# lab6_2020-12-28_18-12-07.net
KiCad netlist of a schematic drawn in EasyEDA
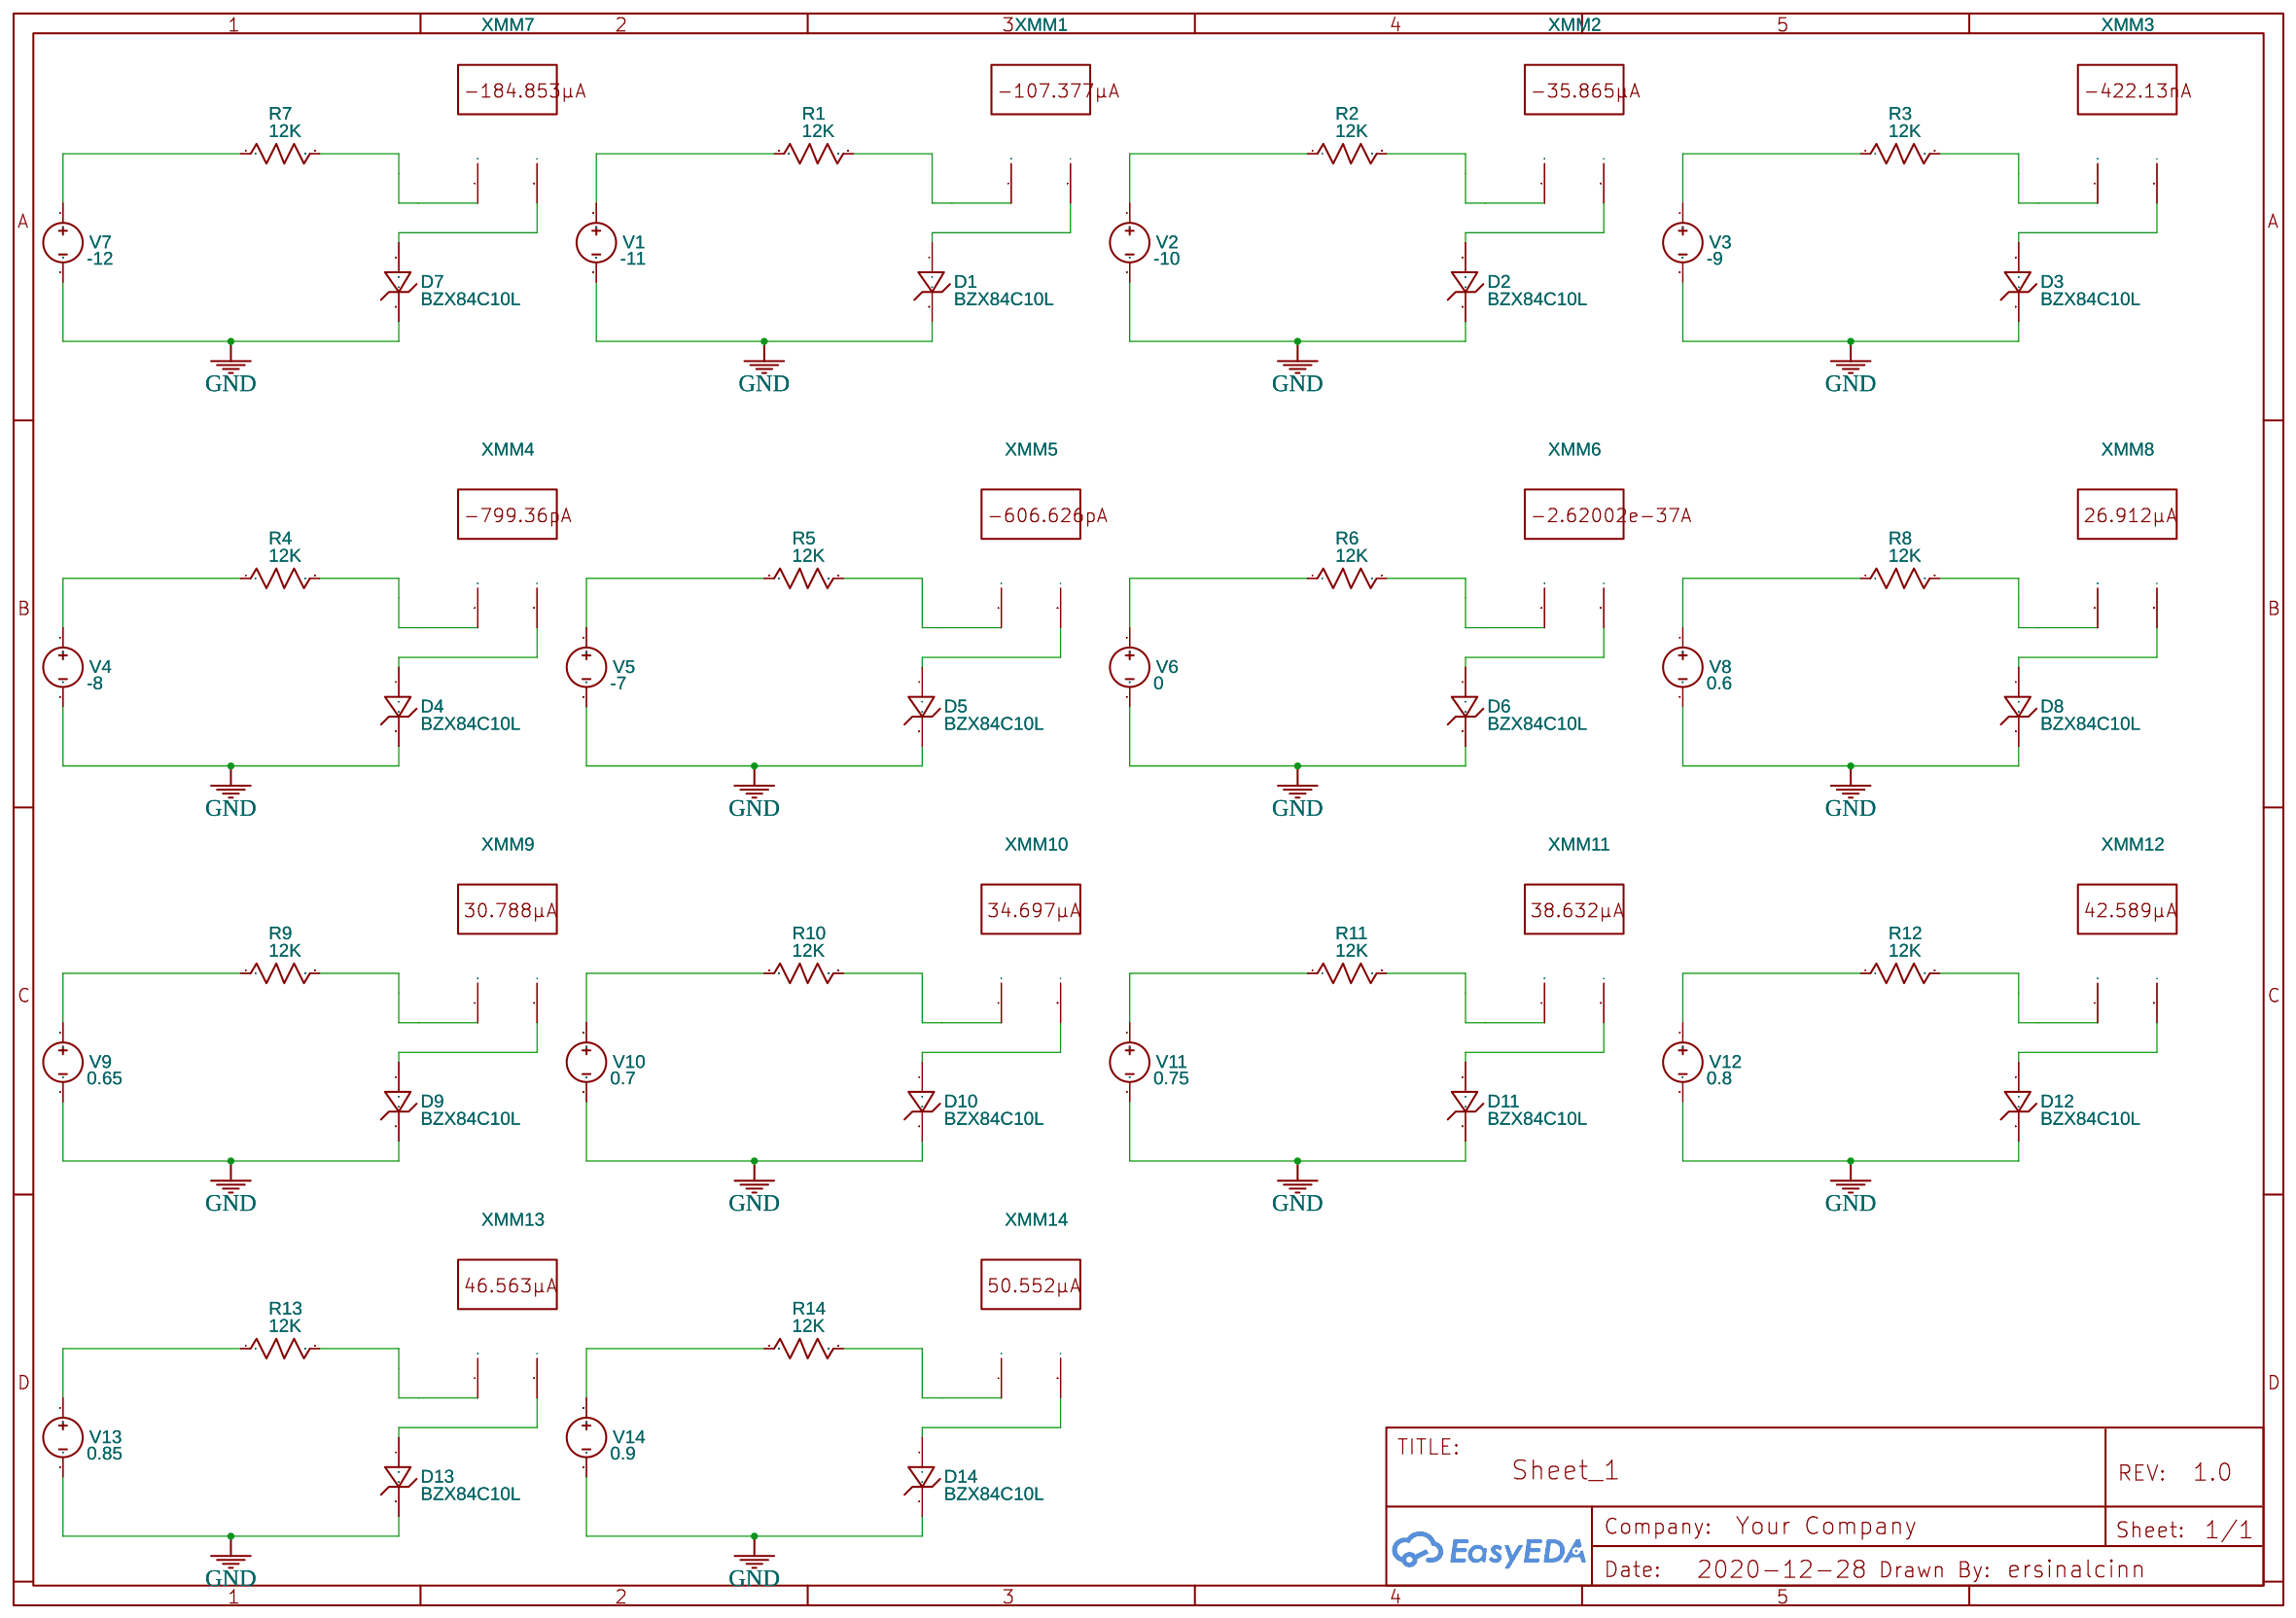
[diagram p0: schematic sheet]

(export (version "E")
  (design (tool "Eeschema 10.0.6"))
  (components
    (comp (ref "D1") (value "BZX84C10L") (libsource (lib "") (part "BZX84C10L")))
    (comp (ref "D2") (value "BZX84C10L") (libsource (lib "") (part "BZX84C10L")))
    (comp (ref "D3") (value "BZX84C10L") (libsource (lib "") (part "BZX84C10L")))
    (comp (ref "D4") (value "BZX84C10L") (libsource (lib "") (part "BZX84C10L")))
    (comp (ref "D5") (value "BZX84C10L") (libsource (lib "") (part "BZX84C10L")))
    (comp (ref "D6") (value "BZX84C10L") (libsource (lib "") (part "BZX84C10L")))
    (comp (ref "D7") (value "BZX84C10L") (libsource (lib "") (part "BZX84C10L")))
    (comp (ref "D8") (value "BZX84C10L") (libsource (lib "") (part "BZX84C10L")))
    (comp (ref "D9") (value "BZX84C10L") (libsource (lib "") (part "BZX84C10L")))
    (comp (ref "D10") (value "BZX84C10L") (libsource (lib "") (part "BZX84C10L")))
    (comp (ref "D11") (value "BZX84C10L") (libsource (lib "") (part "BZX84C10L")))
    (comp (ref "D12") (value "BZX84C10L") (libsource (lib "") (part "BZX84C10L")))
    (comp (ref "D13") (value "BZX84C10L") (libsource (lib "") (part "BZX84C10L")))
    (comp (ref "D14") (value "BZX84C10L") (libsource (lib "") (part "BZX84C10L")))
    (comp (ref "R1") (value "12K") (libsource (lib "") (part "Resistor_US")))
    (comp (ref "R2") (value "12K") (libsource (lib "") (part "Resistor_US")))
    (comp (ref "R3") (value "12K") (libsource (lib "") (part "Resistor_US")))
    (comp (ref "R4") (value "12K") (libsource (lib "") (part "Resistor_US")))
    (comp (ref "R5") (value "12K") (libsource (lib "") (part "Resistor_US")))
    (comp (ref "R6") (value "12K") (libsource (lib "") (part "Resistor_US")))
    (comp (ref "R7") (value "12K") (libsource (lib "") (part "Resistor_US")))
    (comp (ref "R8") (value "12K") (libsource (lib "") (part "Resistor_US")))
    (comp (ref "R9") (value "12K") (libsource (lib "") (part "Resistor_US")))
    (comp (ref "R10") (value "12K") (libsource (lib "") (part "Resistor_US")))
    (comp (ref "R11") (value "12K") (libsource (lib "") (part "Resistor_US")))
    (comp (ref "R12") (value "12K") (libsource (lib "") (part "Resistor_US")))
    (comp (ref "R13") (value "12K") (libsource (lib "") (part "Resistor_US")))
    (comp (ref "R14") (value "12K") (libsource (lib "") (part "Resistor_US")))
    (comp (ref "V1") (value "-11") (libsource (lib "") (part "VDC")))
    (comp (ref "V2") (value "-10") (libsource (lib "") (part "VDC")))
    (comp (ref "V3") (value "-9") (libsource (lib "") (part "VDC")))
    (comp (ref "V4") (value "-8") (libsource (lib "") (part "VDC")))
    (comp (ref "V5") (value "-7") (libsource (lib "") (part "VDC")))
    (comp (ref "V6") (value "0") (libsource (lib "") (part "VDC")))
    (comp (ref "V7") (value "-12") (libsource (lib "") (part "VDC")))
    (comp (ref "V8") (value "0.6") (libsource (lib "") (part "VDC")))
    (comp (ref "V9") (value "0.65") (libsource (lib "") (part "VDC")))
    (comp (ref "V10") (value "0.7") (libsource (lib "") (part "VDC")))
    (comp (ref "V11") (value "0.75") (libsource (lib "") (part "VDC")))
    (comp (ref "V12") (value "0.8") (libsource (lib "") (part "VDC")))
    (comp (ref "V13") (value "0.85") (libsource (lib "") (part "VDC")))
    (comp (ref "V14") (value "0.9") (libsource (lib "") (part "VDC")))
    (comp (ref "XMM1") (value "Multimeter") (libsource (lib "") (part "MULTIMETER_4")))
    (comp (ref "XMM2") (value "Multimeter") (libsource (lib "") (part "MULTIMETER_10")))
    (comp (ref "XMM3") (value "Multimeter") (libsource (lib "") (part "MULTIMETER")))
    (comp (ref "XMM4") (value "Multimeter") (libsource (lib "") (part "MULTIMETER_8")))
    (comp (ref "XMM5") (value "Multimeter") (libsource (lib "") (part "MULTIMETER_9")))
    (comp (ref "XMM6") (value "Multimeter") (libsource (lib "") (part "MULTIMETER_12")))
    (comp (ref "XMM7") (value "Multimeter") (libsource (lib "") (part "MULTIMETER_7")))
    (comp (ref "XMM8") (value "Multimeter") (libsource (lib "") (part "MULTIMETER_3")))
    (comp (ref "XMM9") (value "Multimeter") (libsource (lib "") (part "MULTIMETER_13")))
    (comp (ref "XMM10") (value "Multimeter") (libsource (lib "") (part "MULTIMETER_2")))
    (comp (ref "XMM11") (value "Multimeter") (libsource (lib "") (part "MULTIMETER_5")))
    (comp (ref "XMM12") (value "Multimeter") (libsource (lib "") (part "MULTIMETER_11")))
    (comp (ref "XMM13") (value "Multimeter") (libsource (lib "") (part "MULTIMETER_1")))
    (comp (ref "XMM14") (value "Multimeter") (libsource (lib "") (part "MULTIMETER_6")))
  )
  (nets
    (net (code "1") (name "GND") (class "Default")
      (node (ref "D1") (pin "2") (pinfunction "K_2") (pintype "unspecified"))
      (node (ref "D10") (pin "2") (pinfunction "K_2") (pintype "unspecified"))
      (node (ref "D11") (pin "2") (pinfunction "K_2") (pintype "unspecified"))
      (node (ref "D12") (pin "2") (pinfunction "K_2") (pintype "unspecified"))
      (node (ref "D13") (pin "2") (pinfunction "K_2") (pintype "unspecified"))
      (node (ref "D14") (pin "2") (pinfunction "K_2") (pintype "unspecified"))
      (node (ref "D2") (pin "2") (pinfunction "K_2") (pintype "unspecified"))
      (node (ref "D3") (pin "2") (pinfunction "K_2") (pintype "unspecified"))
      (node (ref "D4") (pin "2") (pinfunction "K_2") (pintype "unspecified"))
      (node (ref "D5") (pin "2") (pinfunction "K_2") (pintype "unspecified"))
      (node (ref "D6") (pin "2") (pinfunction "K_2") (pintype "unspecified"))
      (node (ref "D7") (pin "2") (pinfunction "K_2") (pintype "unspecified"))
      (node (ref "D8") (pin "2") (pinfunction "K_2") (pintype "unspecified"))
      (node (ref "D9") (pin "2") (pinfunction "K_2") (pintype "unspecified"))
      (node (ref "V1") (pin "2") (pinfunction "2_2") (pintype "unspecified"))
      (node (ref "V10") (pin "2") (pinfunction "2_2") (pintype "unspecified"))
      (node (ref "V11") (pin "2") (pinfunction "2_2") (pintype "unspecified"))
      (node (ref "V12") (pin "2") (pinfunction "2_2") (pintype "unspecified"))
      (node (ref "V13") (pin "2") (pinfunction "2_2") (pintype "unspecified"))
      (node (ref "V14") (pin "2") (pinfunction "2_2") (pintype "unspecified"))
      (node (ref "V2") (pin "2") (pinfunction "2_2") (pintype "unspecified"))
      (node (ref "V3") (pin "2") (pinfunction "2_2") (pintype "unspecified"))
      (node (ref "V4") (pin "2") (pinfunction "2_2") (pintype "unspecified"))
      (node (ref "V5") (pin "2") (pinfunction "2_2") (pintype "unspecified"))
      (node (ref "V6") (pin "2") (pinfunction "2_2") (pintype "unspecified"))
      (node (ref "V7") (pin "2") (pinfunction "2_2") (pintype "unspecified"))
      (node (ref "V8") (pin "2") (pinfunction "2_2") (pintype "unspecified"))
      (node (ref "V9") (pin "2") (pinfunction "2_2") (pintype "unspecified"))
    )
    (net (code "2") (name "Net-(D1-A)") (class "Default")
      (node (ref "D1") (pin "1") (pinfunction "A_1") (pintype "unspecified"))
      (node (ref "XMM1") (pin "2") (pinfunction "I_2") (pintype "unspecified"))
    )
    (net (code "3") (name "Net-(D2-A)") (class "Default")
      (node (ref "D2") (pin "1") (pinfunction "A_1") (pintype "unspecified"))
      (node (ref "XMM2") (pin "2") (pinfunction "I_2") (pintype "unspecified"))
    )
    (net (code "4") (name "Net-(D3-A)") (class "Default")
      (node (ref "D3") (pin "1") (pinfunction "A_1") (pintype "unspecified"))
      (node (ref "XMM3") (pin "2") (pinfunction "I_2") (pintype "unspecified"))
    )
    (net (code "5") (name "Net-(D4-A)") (class "Default")
      (node (ref "D4") (pin "1") (pinfunction "A_1") (pintype "unspecified"))
      (node (ref "XMM4") (pin "2") (pinfunction "I_2") (pintype "unspecified"))
    )
    (net (code "6") (name "Net-(D5-A)") (class "Default")
      (node (ref "D5") (pin "1") (pinfunction "A_1") (pintype "unspecified"))
      (node (ref "XMM5") (pin "2") (pinfunction "I_2") (pintype "unspecified"))
    )
    (net (code "7") (name "Net-(D6-A)") (class "Default")
      (node (ref "D6") (pin "1") (pinfunction "A_1") (pintype "unspecified"))
      (node (ref "XMM6") (pin "2") (pinfunction "I_2") (pintype "unspecified"))
    )
    (net (code "8") (name "Net-(D7-A)") (class "Default")
      (node (ref "D7") (pin "1") (pinfunction "A_1") (pintype "unspecified"))
      (node (ref "XMM7") (pin "2") (pinfunction "I_2") (pintype "unspecified"))
    )
    (net (code "9") (name "Net-(D8-A)") (class "Default")
      (node (ref "D8") (pin "1") (pinfunction "A_1") (pintype "unspecified"))
      (node (ref "XMM8") (pin "2") (pinfunction "I_2") (pintype "unspecified"))
    )
    (net (code "10") (name "Net-(D9-A)") (class "Default")
      (node (ref "D9") (pin "1") (pinfunction "A_1") (pintype "unspecified"))
      (node (ref "XMM9") (pin "2") (pinfunction "I_2") (pintype "unspecified"))
    )
    (net (code "11") (name "Net-(D10-A)") (class "Default")
      (node (ref "D10") (pin "1") (pinfunction "A_1") (pintype "unspecified"))
      (node (ref "XMM10") (pin "2") (pinfunction "I_2") (pintype "unspecified"))
    )
    (net (code "12") (name "Net-(D11-A)") (class "Default")
      (node (ref "D11") (pin "1") (pinfunction "A_1") (pintype "unspecified"))
      (node (ref "XMM11") (pin "2") (pinfunction "I_2") (pintype "unspecified"))
    )
    (net (code "13") (name "Net-(D12-A)") (class "Default")
      (node (ref "D12") (pin "1") (pinfunction "A_1") (pintype "unspecified"))
      (node (ref "XMM12") (pin "2") (pinfunction "I_2") (pintype "unspecified"))
    )
    (net (code "14") (name "Net-(D13-A)") (class "Default")
      (node (ref "D13") (pin "1") (pinfunction "A_1") (pintype "unspecified"))
      (node (ref "XMM13") (pin "2") (pinfunction "I_2") (pintype "unspecified"))
    )
    (net (code "15") (name "Net-(D14-A)") (class "Default")
      (node (ref "D14") (pin "1") (pinfunction "A_1") (pintype "unspecified"))
      (node (ref "XMM14") (pin "2") (pinfunction "I_2") (pintype "unspecified"))
    )
    (net (code "16") (name "Net-(R1-Pad1)") (class "Default")
      (node (ref "R1") (pin "1") (pinfunction "1_1") (pintype "unspecified"))
      (node (ref "V1") (pin "1") (pinfunction "1_1") (pintype "unspecified"))
    )
    (net (code "17") (name "Net-(R2-Pad1)") (class "Default")
      (node (ref "R2") (pin "1") (pinfunction "1_1") (pintype "unspecified"))
      (node (ref "V2") (pin "1") (pinfunction "1_1") (pintype "unspecified"))
    )
    (net (code "18") (name "Net-(R3-Pad1)") (class "Default")
      (node (ref "R3") (pin "1") (pinfunction "1_1") (pintype "unspecified"))
      (node (ref "V3") (pin "1") (pinfunction "1_1") (pintype "unspecified"))
    )
    (net (code "19") (name "Net-(R4-Pad1)") (class "Default")
      (node (ref "R4") (pin "1") (pinfunction "1_1") (pintype "unspecified"))
      (node (ref "V4") (pin "1") (pinfunction "1_1") (pintype "unspecified"))
    )
    (net (code "20") (name "Net-(R5-Pad1)") (class "Default")
      (node (ref "R5") (pin "1") (pinfunction "1_1") (pintype "unspecified"))
      (node (ref "V5") (pin "1") (pinfunction "1_1") (pintype "unspecified"))
    )
    (net (code "21") (name "Net-(R6-Pad1)") (class "Default")
      (node (ref "R6") (pin "1") (pinfunction "1_1") (pintype "unspecified"))
      (node (ref "V6") (pin "1") (pinfunction "1_1") (pintype "unspecified"))
    )
    (net (code "22") (name "Net-(R7-Pad1)") (class "Default")
      (node (ref "R7") (pin "1") (pinfunction "1_1") (pintype "unspecified"))
      (node (ref "V7") (pin "1") (pinfunction "1_1") (pintype "unspecified"))
    )
    (net (code "23") (name "Net-(R8-Pad1)") (class "Default")
      (node (ref "R8") (pin "1") (pinfunction "1_1") (pintype "unspecified"))
      (node (ref "V8") (pin "1") (pinfunction "1_1") (pintype "unspecified"))
    )
    (net (code "24") (name "Net-(R9-Pad1)") (class "Default")
      (node (ref "R9") (pin "1") (pinfunction "1_1") (pintype "unspecified"))
      (node (ref "V9") (pin "1") (pinfunction "1_1") (pintype "unspecified"))
    )
    (net (code "25") (name "Net-(R10-Pad1)") (class "Default")
      (node (ref "R10") (pin "1") (pinfunction "1_1") (pintype "unspecified"))
      (node (ref "V10") (pin "1") (pinfunction "1_1") (pintype "unspecified"))
    )
    (net (code "26") (name "Net-(R11-Pad1)") (class "Default")
      (node (ref "R11") (pin "1") (pinfunction "1_1") (pintype "unspecified"))
      (node (ref "V11") (pin "1") (pinfunction "1_1") (pintype "unspecified"))
    )
    (net (code "27") (name "Net-(R12-Pad1)") (class "Default")
      (node (ref "R12") (pin "1") (pinfunction "1_1") (pintype "unspecified"))
      (node (ref "V12") (pin "1") (pinfunction "1_1") (pintype "unspecified"))
    )
    (net (code "28") (name "Net-(R13-Pad1)") (class "Default")
      (node (ref "R13") (pin "1") (pinfunction "1_1") (pintype "unspecified"))
      (node (ref "V13") (pin "1") (pinfunction "1_1") (pintype "unspecified"))
    )
    (net (code "29") (name "Net-(R14-Pad1)") (class "Default")
      (node (ref "R14") (pin "1") (pinfunction "1_1") (pintype "unspecified"))
      (node (ref "V14") (pin "1") (pinfunction "1_1") (pintype "unspecified"))
    )
    (net (code "30") (name "Net-(XMM1-+)") (class "Default")
      (node (ref "R1") (pin "2") (pinfunction "2_2") (pintype "unspecified"))
      (node (ref "XMM1") (pin "1") (pinfunction "+_1") (pintype "unspecified"))
    )
    (net (code "31") (name "Net-(XMM2-+)") (class "Default")
      (node (ref "R2") (pin "2") (pinfunction "2_2") (pintype "unspecified"))
      (node (ref "XMM2") (pin "1") (pinfunction "+_1") (pintype "unspecified"))
    )
    (net (code "32") (name "Net-(XMM3-+)") (class "Default")
      (node (ref "R3") (pin "2") (pinfunction "2_2") (pintype "unspecified"))
      (node (ref "XMM3") (pin "1") (pinfunction "+_1") (pintype "unspecified"))
    )
    (net (code "33") (name "Net-(XMM4-+)") (class "Default")
      (node (ref "R4") (pin "2") (pinfunction "2_2") (pintype "unspecified"))
      (node (ref "XMM4") (pin "1") (pinfunction "+_1") (pintype "unspecified"))
    )
    (net (code "34") (name "Net-(XMM5-+)") (class "Default")
      (node (ref "R5") (pin "2") (pinfunction "2_2") (pintype "unspecified"))
      (node (ref "XMM5") (pin "1") (pinfunction "+_1") (pintype "unspecified"))
    )
    (net (code "35") (name "Net-(XMM6-+)") (class "Default")
      (node (ref "R6") (pin "2") (pinfunction "2_2") (pintype "unspecified"))
      (node (ref "XMM6") (pin "1") (pinfunction "+_1") (pintype "unspecified"))
    )
    (net (code "36") (name "Net-(XMM7-+)") (class "Default")
      (node (ref "R7") (pin "2") (pinfunction "2_2") (pintype "unspecified"))
      (node (ref "XMM7") (pin "1") (pinfunction "+_1") (pintype "unspecified"))
    )
    (net (code "37") (name "Net-(XMM8-+)") (class "Default")
      (node (ref "R8") (pin "2") (pinfunction "2_2") (pintype "unspecified"))
      (node (ref "XMM8") (pin "1") (pinfunction "+_1") (pintype "unspecified"))
    )
    (net (code "38") (name "Net-(XMM9-+)") (class "Default")
      (node (ref "R9") (pin "2") (pinfunction "2_2") (pintype "unspecified"))
      (node (ref "XMM9") (pin "1") (pinfunction "+_1") (pintype "unspecified"))
    )
    (net (code "39") (name "Net-(XMM10-+)") (class "Default")
      (node (ref "R10") (pin "2") (pinfunction "2_2") (pintype "unspecified"))
      (node (ref "XMM10") (pin "1") (pinfunction "+_1") (pintype "unspecified"))
    )
    (net (code "40") (name "Net-(XMM11-+)") (class "Default")
      (node (ref "R11") (pin "2") (pinfunction "2_2") (pintype "unspecified"))
      (node (ref "XMM11") (pin "1") (pinfunction "+_1") (pintype "unspecified"))
    )
    (net (code "41") (name "Net-(XMM12-+)") (class "Default")
      (node (ref "R12") (pin "2") (pinfunction "2_2") (pintype "unspecified"))
      (node (ref "XMM12") (pin "1") (pinfunction "+_1") (pintype "unspecified"))
    )
    (net (code "42") (name "Net-(XMM13-+)") (class "Default")
      (node (ref "R13") (pin "2") (pinfunction "2_2") (pintype "unspecified"))
      (node (ref "XMM13") (pin "1") (pinfunction "+_1") (pintype "unspecified"))
    )
    (net (code "43") (name "Net-(XMM14-+)") (class "Default")
      (node (ref "R14") (pin "2") (pinfunction "2_2") (pintype "unspecified"))
      (node (ref "XMM14") (pin "1") (pinfunction "+_1") (pintype "unspecified"))
    )
  )
)
